# Board_v_02b.net
KiCad netlist of a schematic drawn in EAGLE
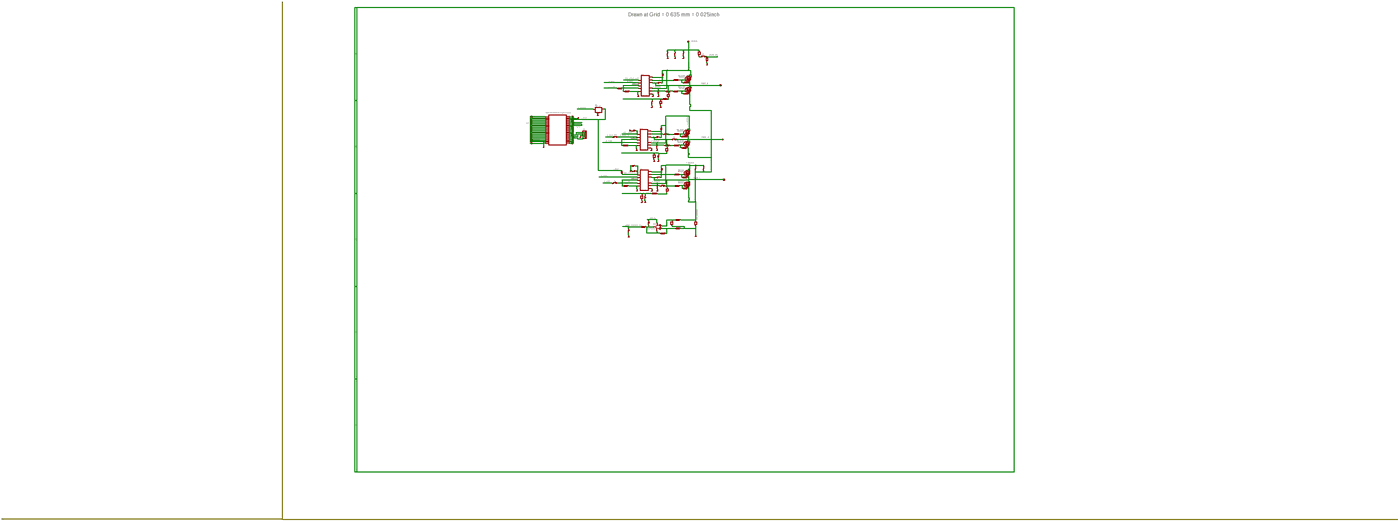
[diagram p0: schematic, sheet 1, overview]
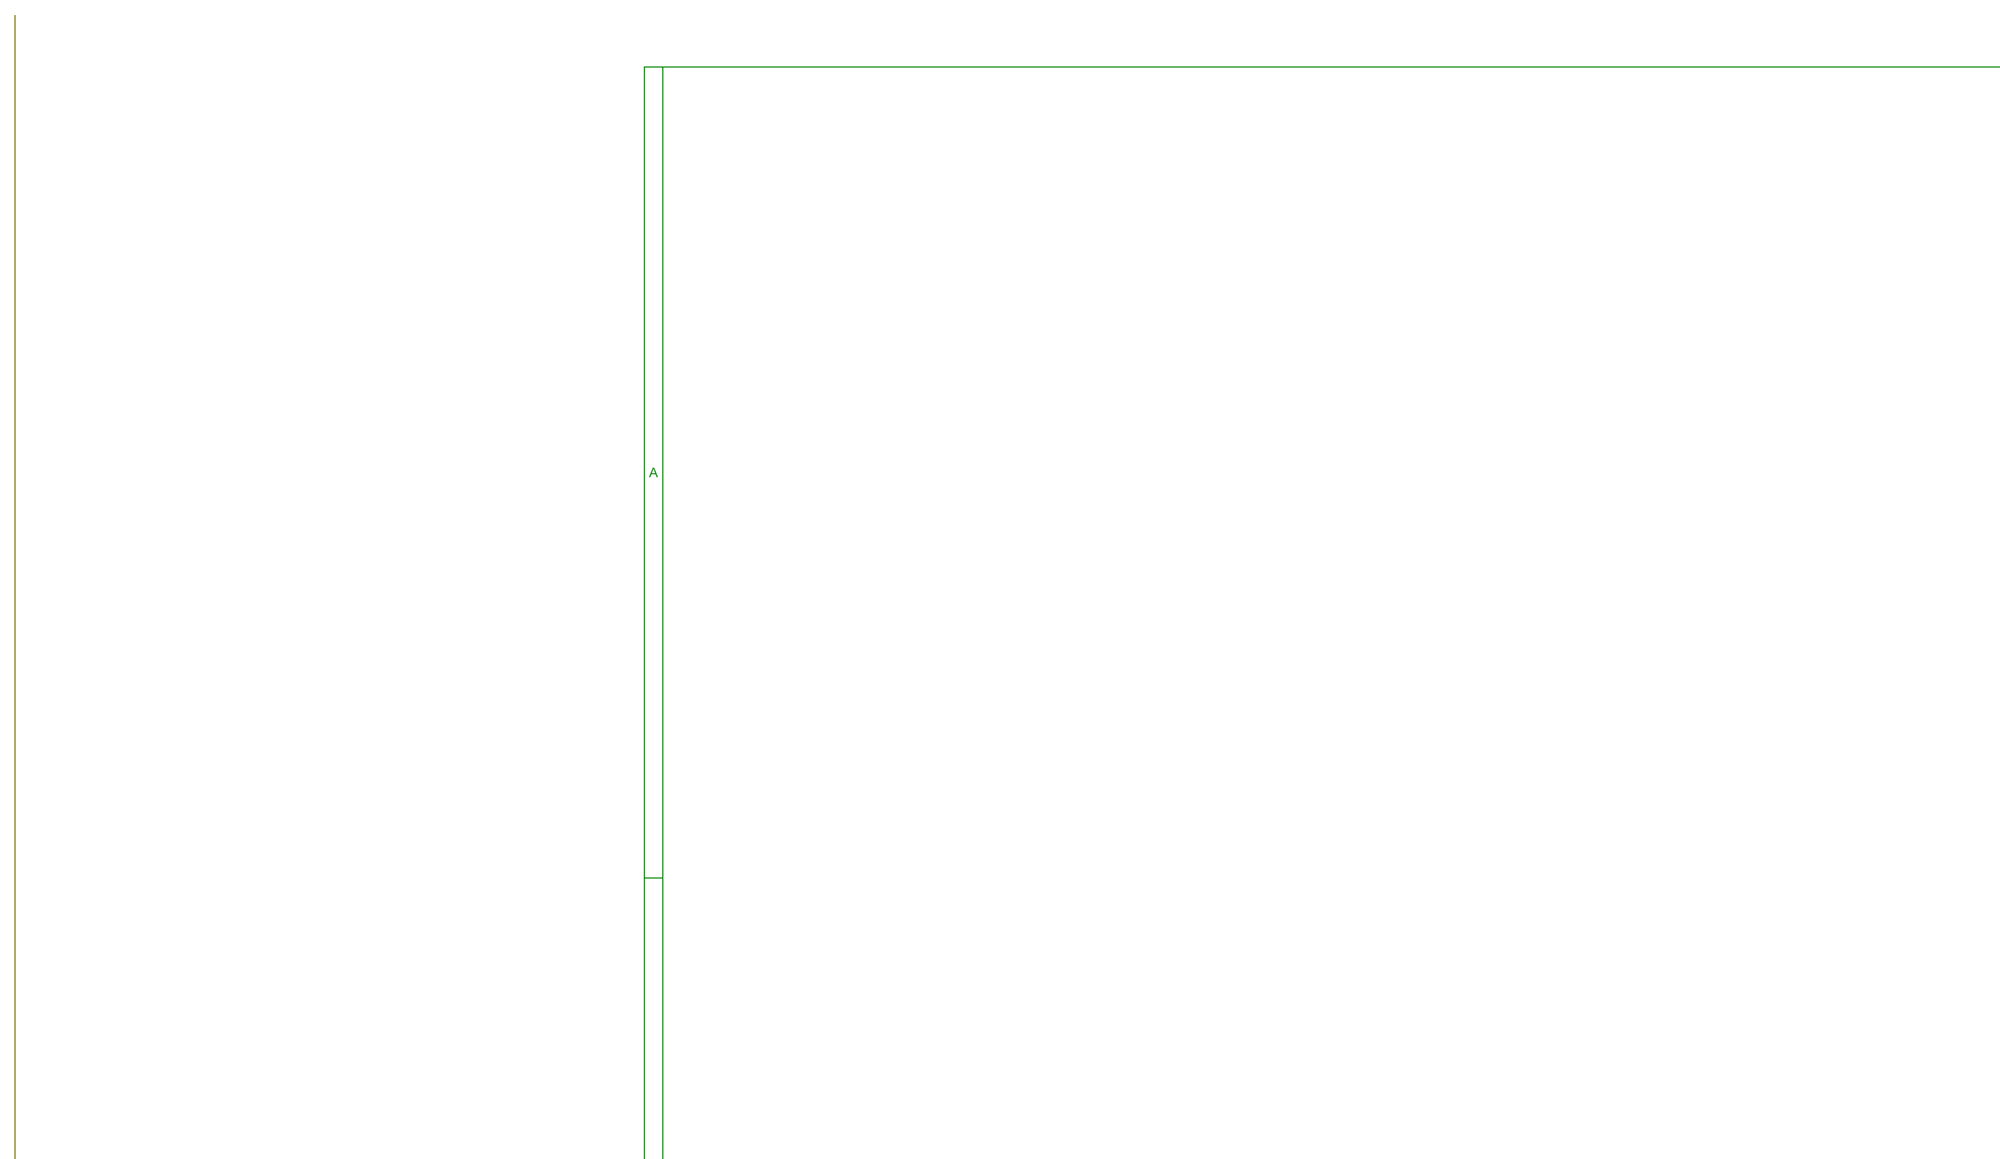
[diagram p1: schematic, sheet 1, part 1 of 7]
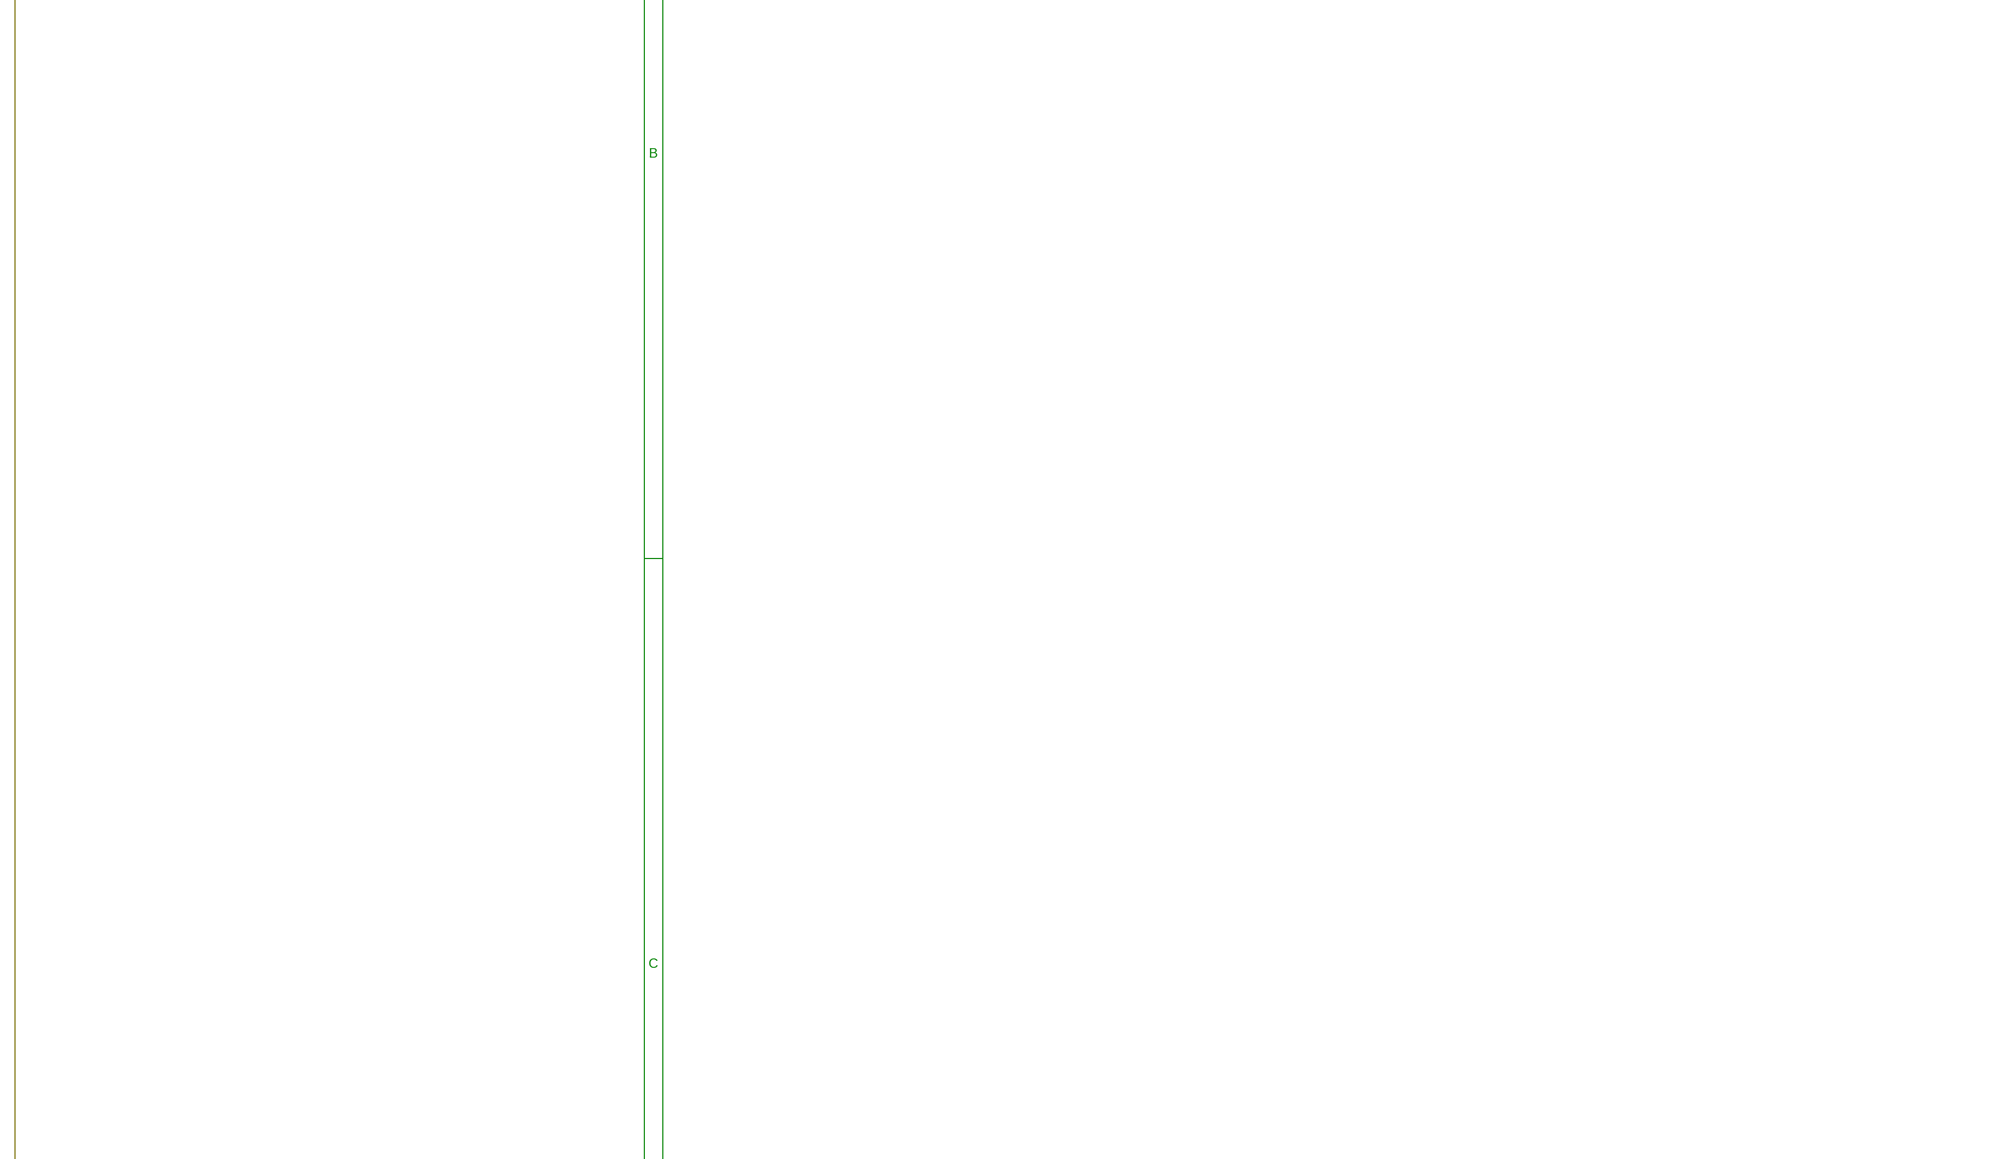
[diagram p2: schematic, sheet 1, part 2 of 7]
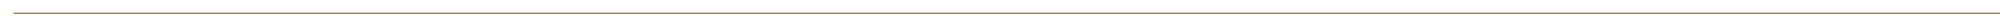
[diagram p3: schematic, sheet 1, part 3 of 7]
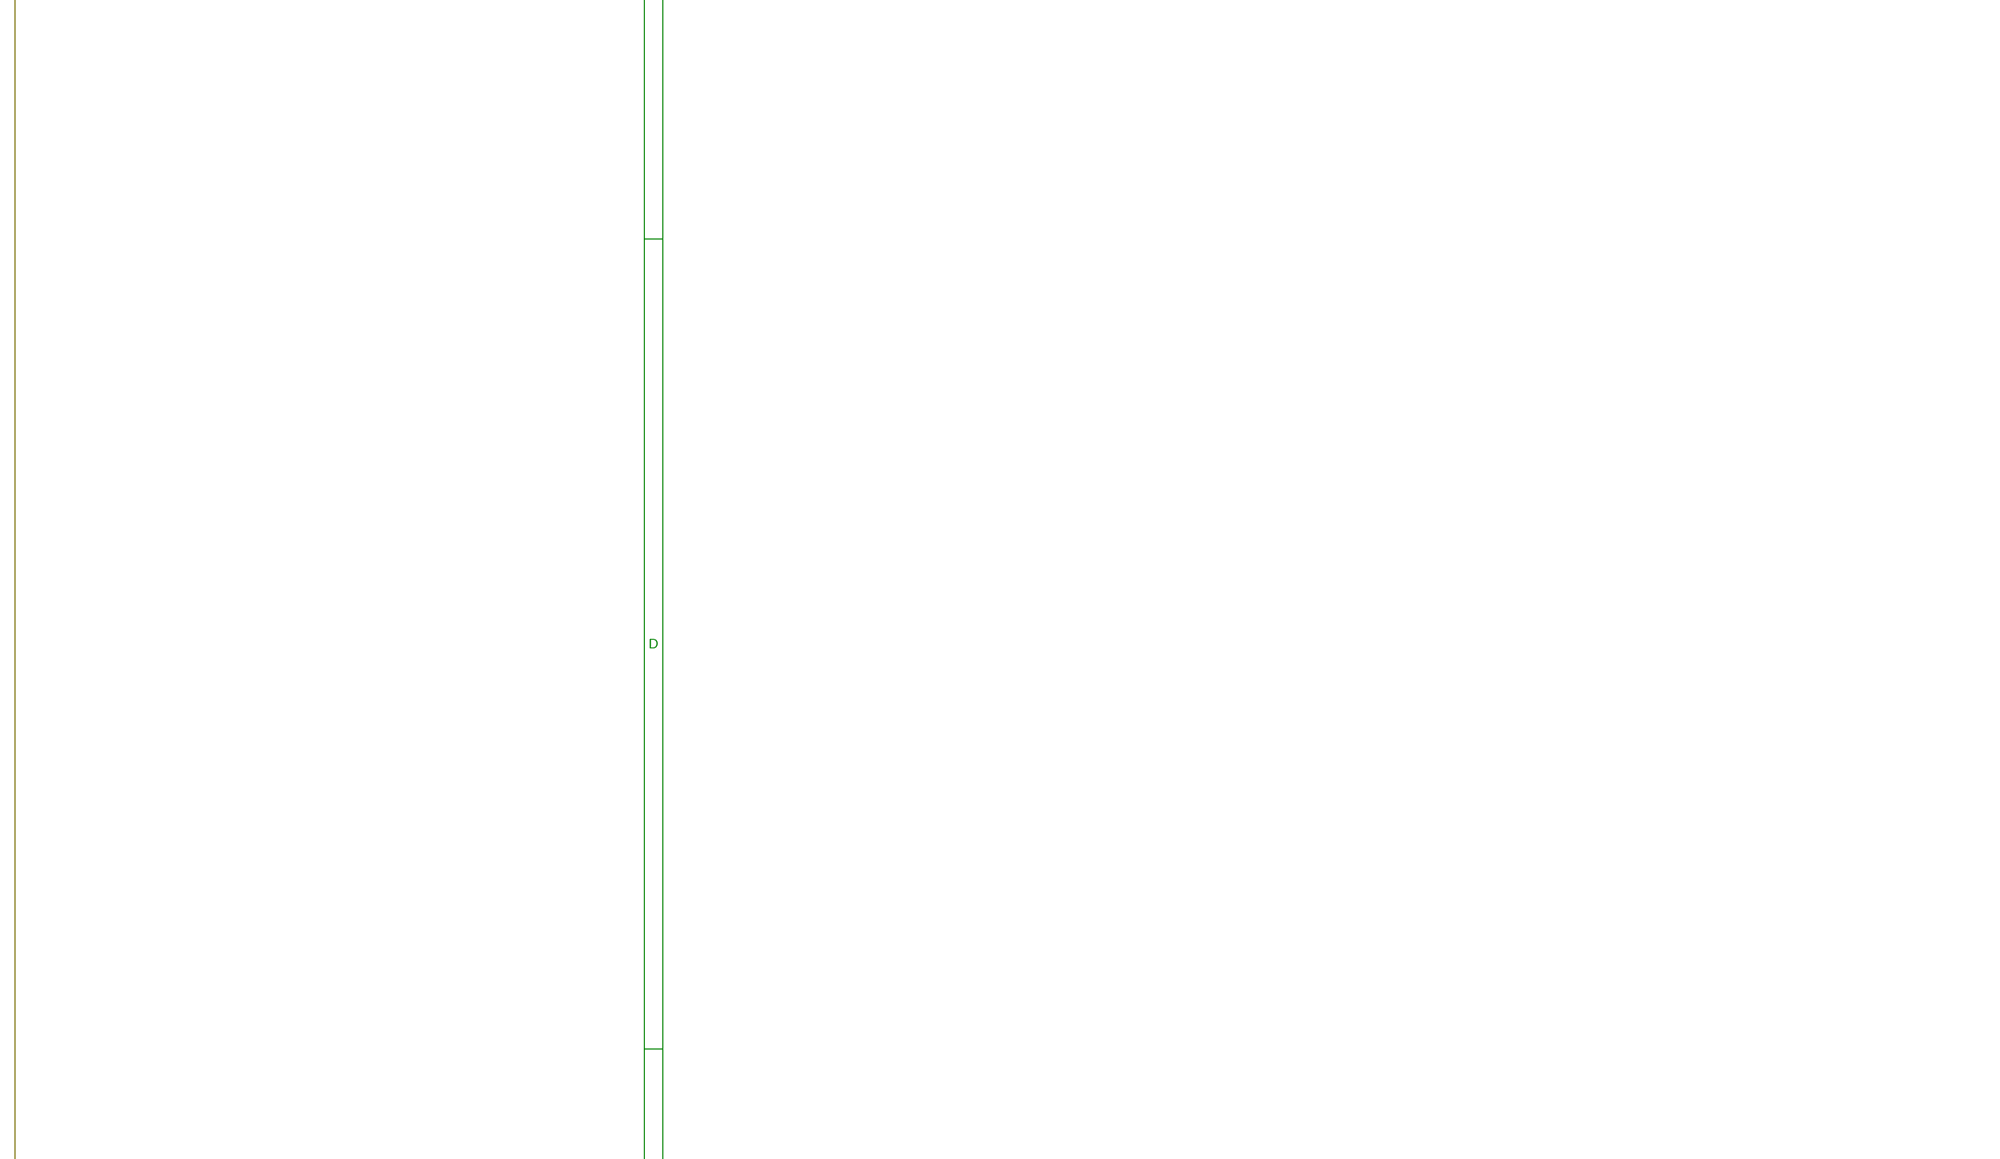
[diagram p4: schematic, sheet 1, part 4 of 7]
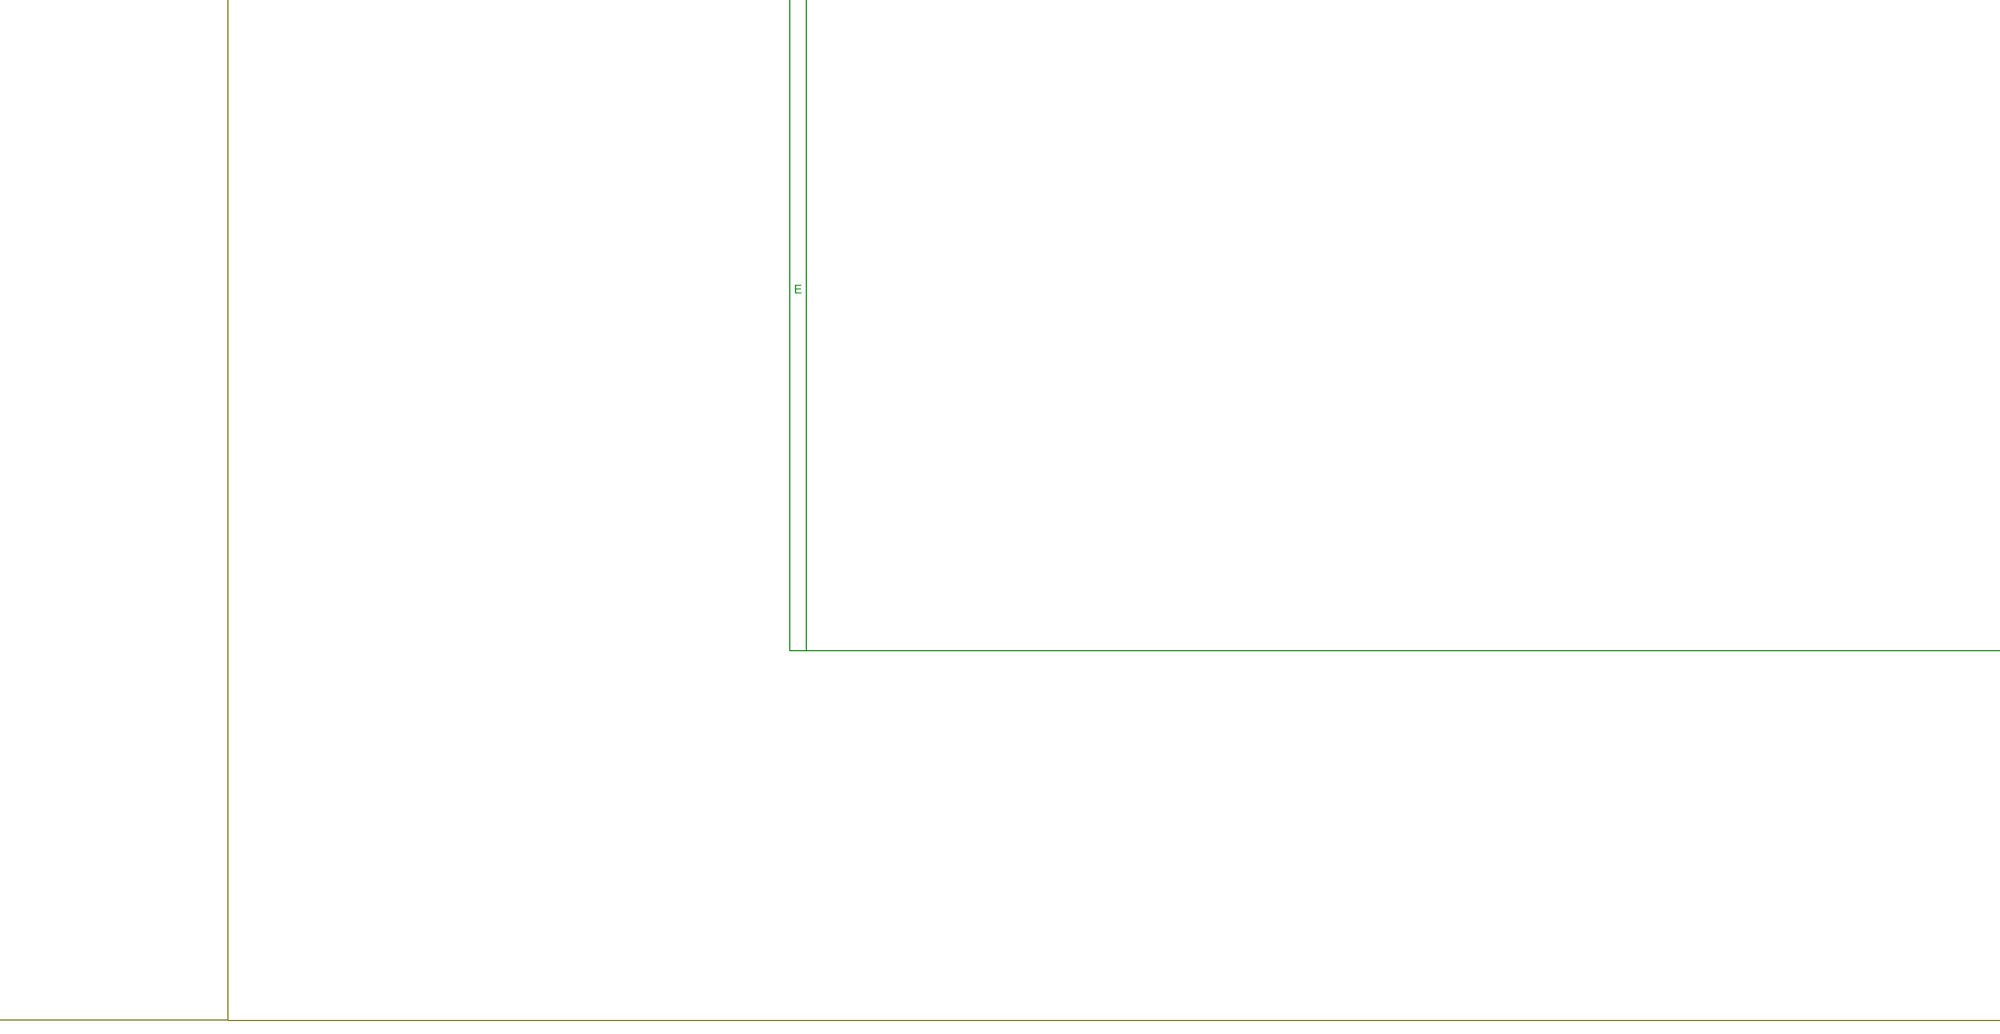
[diagram p5: schematic, sheet 1, part 5 of 7]
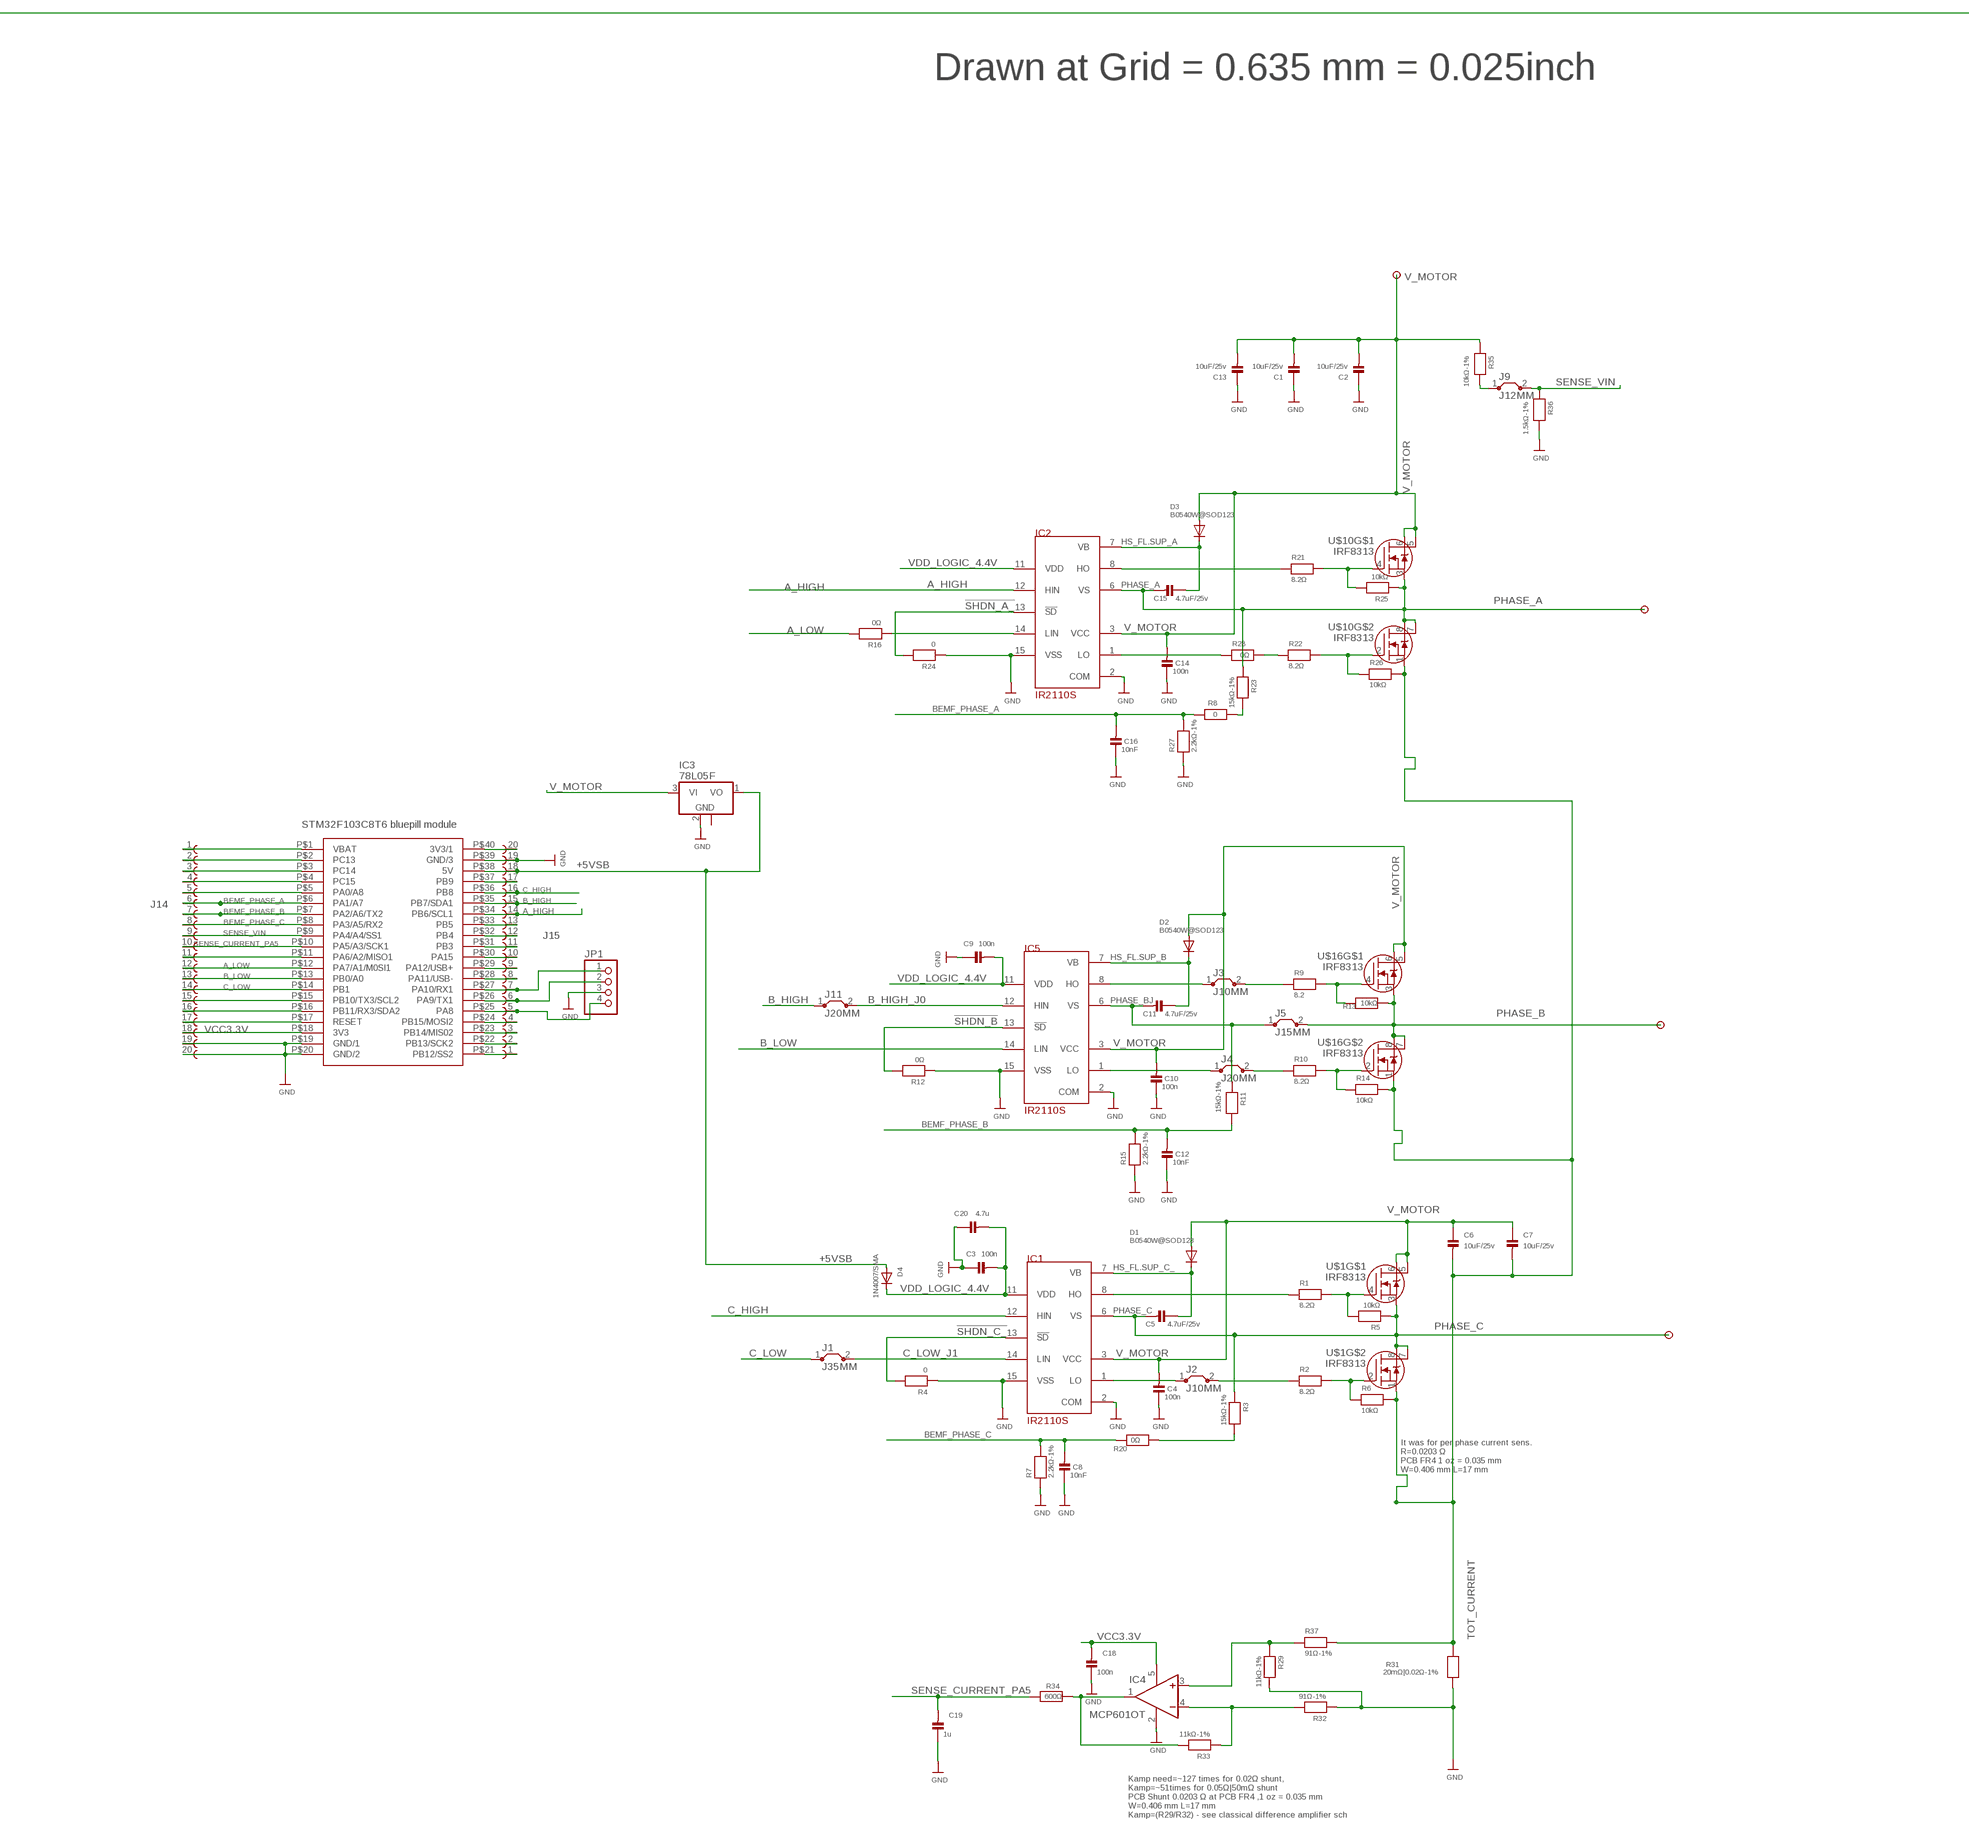
[diagram p6: schematic, sheet 1, part 6 of 7]
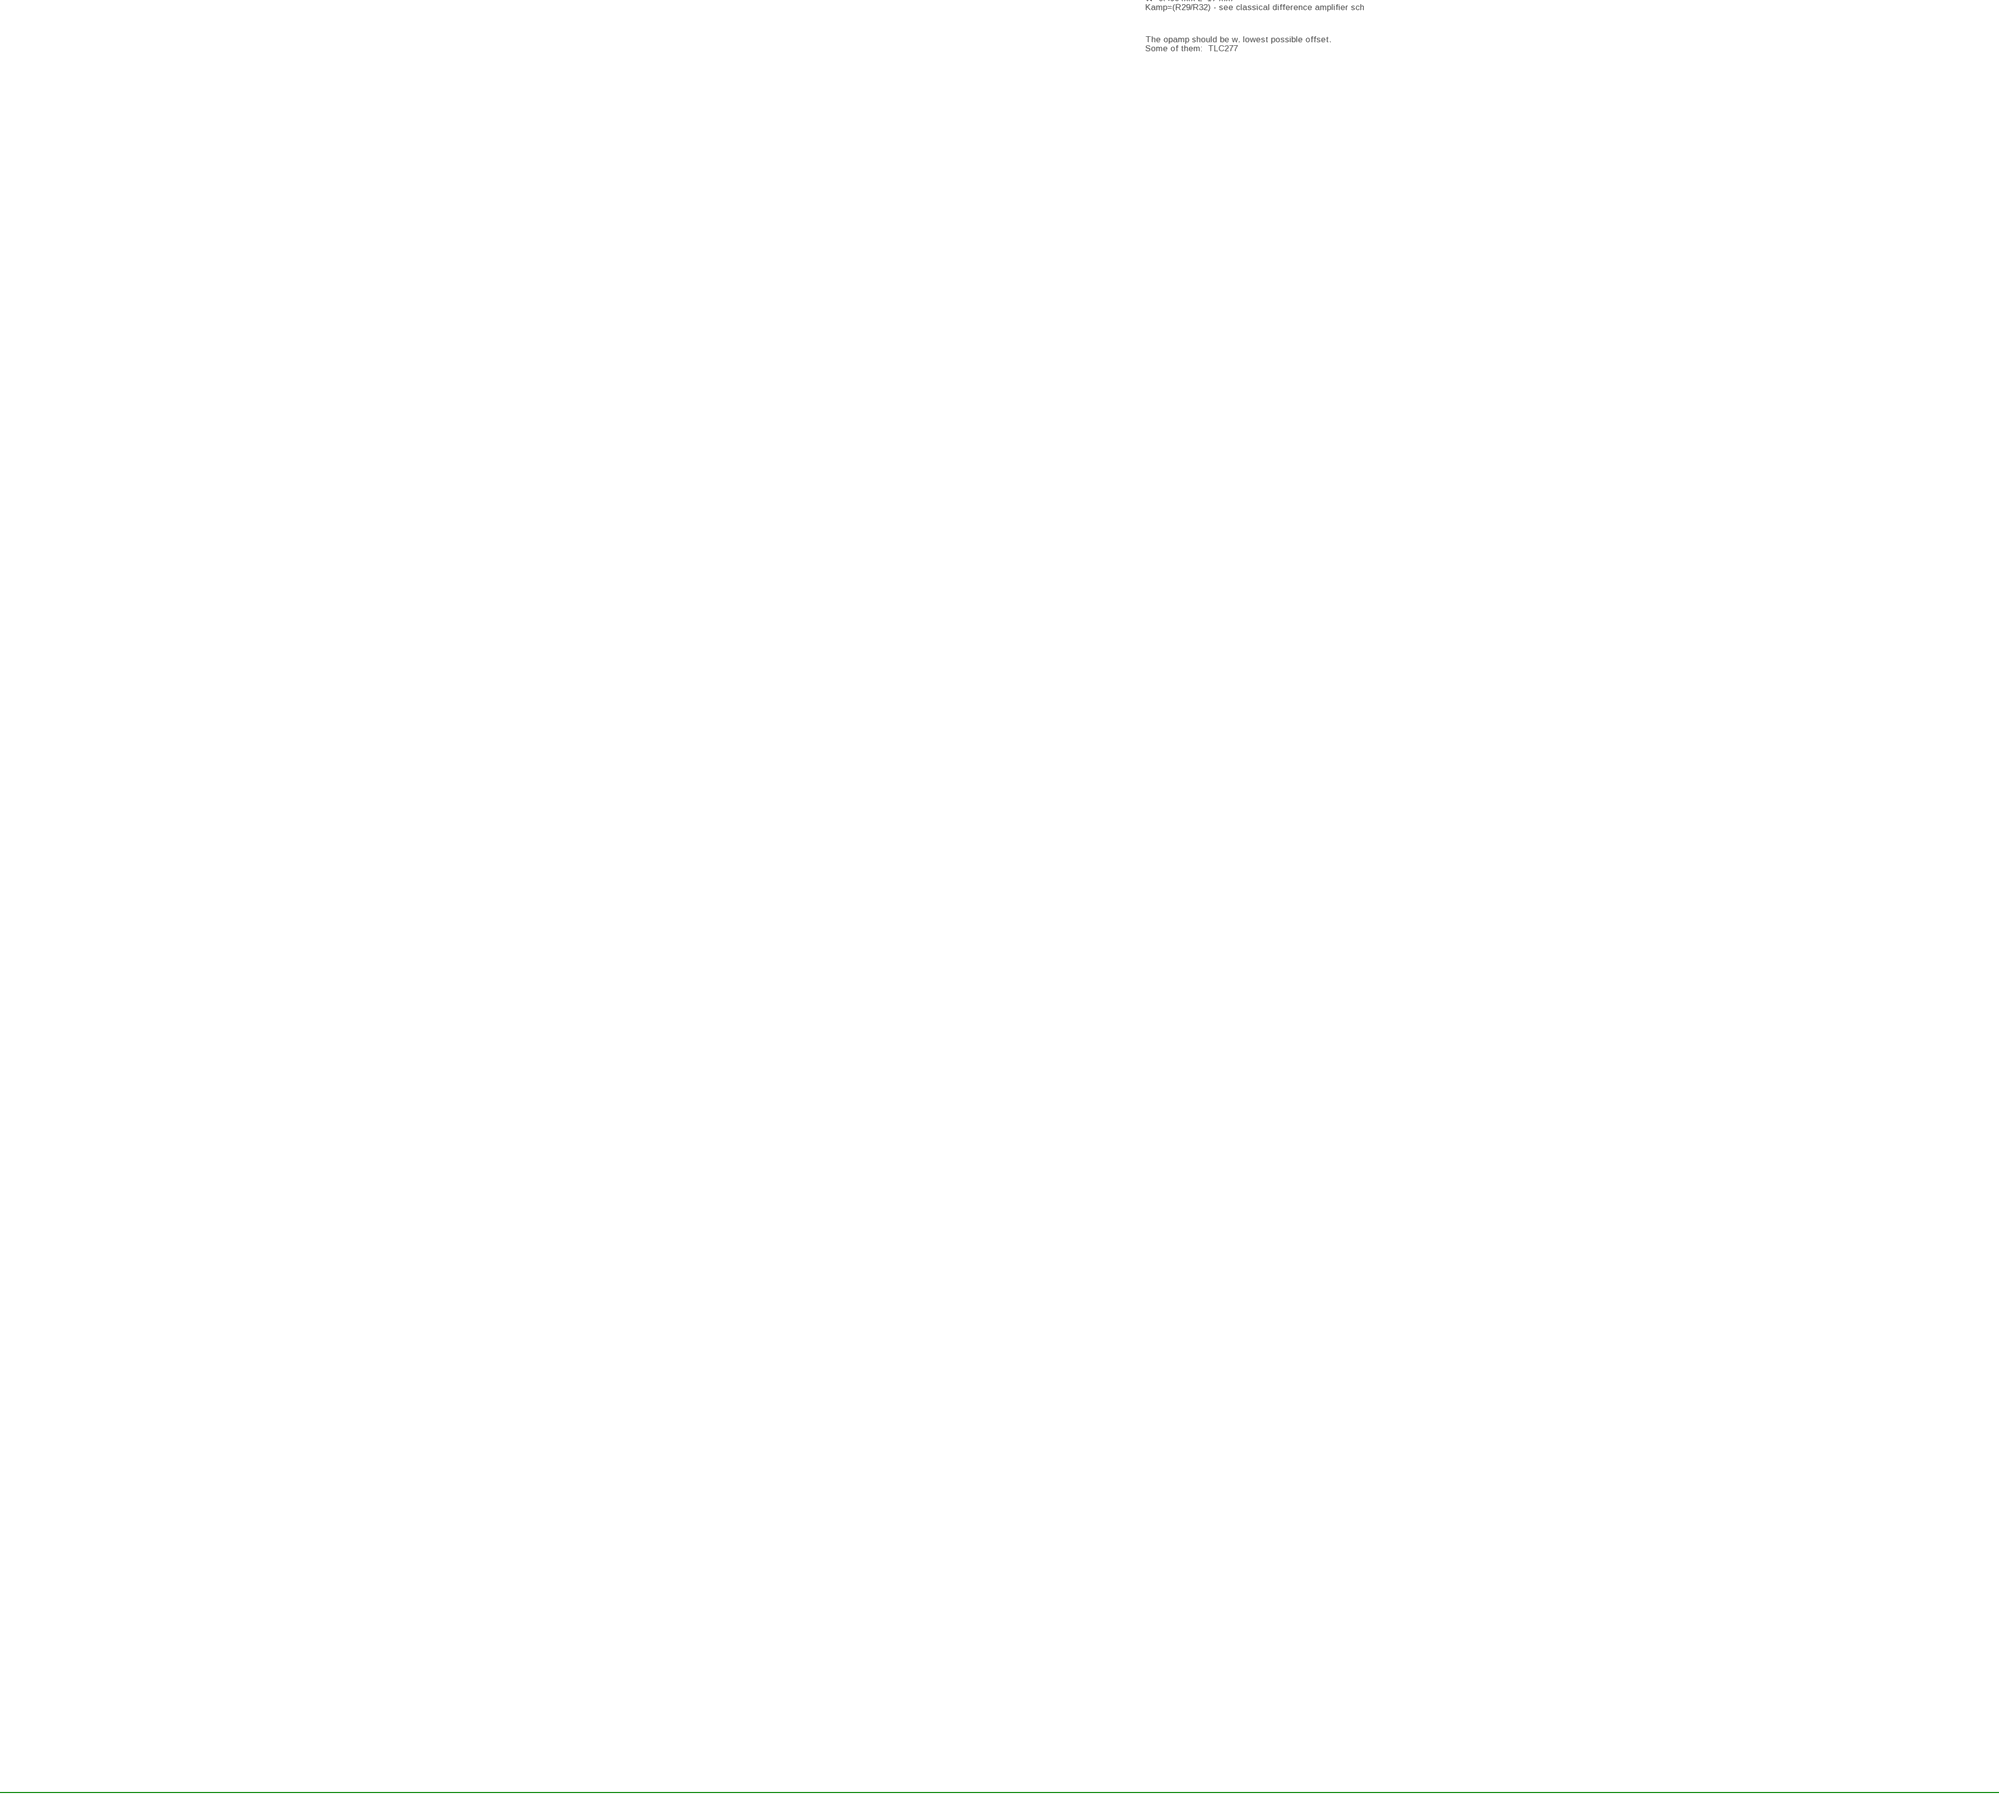
[diagram p7: schematic, sheet 1, part 7 of 7]

(export (version "E")
  (design (tool "Eeschema 10.0.6"))
  (components
    (comp (ref "BLUEPILL-STM32F103C8T6_MODULE")
      (value "BLUEPILL")
      (footprint "eagle-import:40-DIP-BLUE-PIL")
      (fields (field (name "NAME1") "STM32F103C8T6 bluepill module"))
      (libsource (lib "eagle-import") (part "BLUEPILL"))
    )
    (comp (ref "C1")
      (value "10uF/25v")
      (footprint "eagle-import:_0805MP")
      (libsource (lib "eagle-import") (part "CAP_CERAMIC_0805MP"))
    )
    (comp (ref "C2")
      (value "10uF/25v")
      (footprint "eagle-import:_0805MP")
      (libsource (lib "eagle-import") (part "CAP_CERAMIC_0805MP"))
    )
    (comp (ref "C3")
      (value "100n")
      (footprint "eagle-import:_0805MP")
      (libsource (lib "eagle-import") (part "CAP_CERAMIC_0805MP"))
    )
    (comp (ref "C4")
      (value "100n")
      (footprint "eagle-import:_0603MP")
      (libsource (lib "eagle-import") (part "CAP_CERAMIC_0603MP"))
    )
    (comp (ref "C5")
      (value "4.7uF/25v")
      (footprint "eagle-import:_0805MP")
      (libsource (lib "eagle-import") (part "CAP_CERAMIC_0805MP"))
    )
    (comp (ref "C6")
      (value "10uF/25v")
      (footprint "eagle-import:_0805MP")
      (libsource (lib "eagle-import") (part "CAP_CERAMIC_0805MP"))
    )
    (comp (ref "C7")
      (value "10uF/25v")
      (footprint "eagle-import:_0805MP")
      (libsource (lib "eagle-import") (part "CAP_CERAMIC_0805MP"))
    )
    (comp (ref "C8")
      (value "10nF")
      (footprint "eagle-import:_0805MP")
      (libsource (lib "eagle-import") (part "CAP_CERAMIC_0805MP"))
    )
    (comp (ref "C9")
      (value "100n")
      (footprint "eagle-import:_0603MP")
      (libsource (lib "eagle-import") (part "CAP_CERAMIC_0603MP"))
    )
    (comp (ref "C10")
      (value "100n")
      (footprint "eagle-import:_0603MP")
      (libsource (lib "eagle-import") (part "CAP_CERAMIC_0603MP"))
    )
    (comp (ref "C11")
      (value "4.7uF/25v")
      (footprint "eagle-import:_0805MP")
      (libsource (lib "eagle-import") (part "CAP_CERAMIC_0805MP"))
    )
    (comp (ref "C12")
      (value "10nF")
      (footprint "eagle-import:_0805MP")
      (libsource (lib "eagle-import") (part "CAP_CERAMIC_0805MP"))
    )
    (comp (ref "C13")
      (value "10uF/25v")
      (footprint "eagle-import:_0805MP")
      (libsource (lib "eagle-import") (part "CAP_CERAMIC_0805MP"))
    )
    (comp (ref "C14")
      (value "100n")
      (footprint "eagle-import:_0603MP")
      (libsource (lib "eagle-import") (part "CAP_CERAMIC_0603MP"))
    )
    (comp (ref "C15")
      (value "4.7uF/25v")
      (footprint "eagle-import:_0805MP")
      (libsource (lib "eagle-import") (part "CAP_CERAMIC_0805MP"))
    )
    (comp (ref "C16")
      (value "10nF")
      (footprint "eagle-import:_0805MP")
      (libsource (lib "eagle-import") (part "CAP_CERAMIC_0805MP"))
    )
    (comp (ref "C18")
      (value "100n")
      (footprint "eagle-import:_0805MP")
      (libsource (lib "eagle-import") (part "CAP_CERAMIC_0805MP"))
    )
    (comp (ref "C19")
      (value "1u")
      (footprint "eagle-import:_0805MP")
      (libsource (lib "eagle-import") (part "CAP_CERAMIC_0805MP"))
    )
    (comp (ref "C20")
      (value "4.7u")
      (footprint "eagle-import:_0805MP")
      (libsource (lib "eagle-import") (part "CAP_CERAMIC_0805MP"))
    )
    (comp (ref "D1")
      (value "B0540W@SOD123")
      (footprint "eagle-import:SOD-123")
      (libsource (lib "eagle-import") (part "DIODESOD-123"))
    )
    (comp (ref "D2")
      (value "B0540W@SOD123")
      (footprint "eagle-import:SOD-123")
      (libsource (lib "eagle-import") (part "DIODESOD-123"))
    )
    (comp (ref "D3")
      (value "B0540W@SOD123")
      (footprint "eagle-import:SOD-123")
      (libsource (lib "eagle-import") (part "DIODESOD-123"))
    )
    (comp (ref "D4")
      (value "1N4007/SMA")
      (footprint "eagle-import:SMADIODE")
      (libsource (lib "eagle-import") (part "DIODESMA"))
    )
    (comp (ref "IC1")
      (value "IR2110S")
      (footprint "eagle-import:SO-16DW")
      (libsource (lib "eagle-import") (part "IR2110S"))
    )
    (comp (ref "IC2")
      (value "IR2110S")
      (footprint "eagle-import:SO-16DW")
      (libsource (lib "eagle-import") (part "IR2110S"))
    )
    (comp (ref "IC3")
      (value "78L05F")
      (footprint "eagle-import:SOT89")
      (libsource (lib "eagle-import") (part "78LF05"))
    )
    (comp (ref "IC4")
      (value "MCP601OT")
      (footprint "eagle-import:SOT23-5")
      (libsource (lib "eagle-import") (part "MCP601OT"))
    )
    (comp (ref "IC5")
      (value "IR2110S")
      (footprint "eagle-import:SO-16DW")
      (libsource (lib "eagle-import") (part "IR2110S"))
    )
    (comp (ref "J1")
      (value "J35MM")
      (footprint "eagle-import:J35MM")
      (libsource (lib "eagle-import") (part "J35MM"))
    )
    (comp (ref "J2")
      (value "J10MM")
      (footprint "eagle-import:10")
      (libsource (lib "eagle-import") (part "jumper_J10MM"))
    )
    (comp (ref "J3")
      (value "J10MM")
      (footprint "eagle-import:10")
      (libsource (lib "eagle-import") (part "jumper_J10MM"))
    )
    (comp (ref "J4")
      (value "J20MM")
      (footprint "eagle-import:20")
      (libsource (lib "eagle-import") (part "jumper_J20MM"))
    )
    (comp (ref "J5")
      (value "J15MM")
      (footprint "eagle-import:15")
      (libsource (lib "eagle-import") (part "jumper_J15MM"))
    )
    (comp (ref "J9")
      (value "J12MM")
      (footprint "eagle-import:12")
      (libsource (lib "eagle-import") (part "jumper_J12MM"))
    )
    (comp (ref "J11")
      (value "J20MM")
      (footprint "eagle-import:20")
      (libsource (lib "eagle-import") (part "jumper_J20MM"))
    )
    (comp (ref "J14")
      (value "61002013321")
      (footprint "eagle-import:CON-20PIN-SMD-MANUALLY-BENT-FROM-NON-SMD")
      (libsource (lib "eagle-import") (part "61002013321"))
    )
    (comp (ref "J15")
      (value "61002013321")
      (footprint "eagle-import:CON-20PIN-SMD-MANUALLY-BENT-FROM-NON-SMD")
      (libsource (lib "eagle-import") (part "61002013321"))
    )
    (comp (ref "JP1")
      (value "PINHD-1X04_2.54-SMD")
      (footprint "eagle-import:1X04SMD")
      (libsource (lib "eagle-import") (part "PINHD-1X04_2.54-SMD"))
    )
    (comp (ref "PHASE_A")
      (value "PHASE_A")
      (footprint "eagle-import:PAD")
      (libsource (lib "eagle-import") (part "PAD"))
    )
    (comp (ref "PHASE_B")
      (value "PHASE_B")
      (footprint "eagle-import:PAD")
      (libsource (lib "eagle-import") (part "PAD"))
    )
    (comp (ref "PHASE_C")
      (value "PHASE_C")
      (footprint "eagle-import:PAD")
      (libsource (lib "eagle-import") (part "PAD"))
    )
    (comp (ref "R1")
      (value "8.2Ω")
      (footprint "eagle-import:_0805MP")
      (libsource (lib "eagle-import") (part "RESISTOR_0805MP"))
    )
    (comp (ref "R2")
      (value "8.2Ω")
      (footprint "eagle-import:_0805MP")
      (libsource (lib "eagle-import") (part "RESISTOR_0805MP"))
    )
    (comp (ref "R3")
      (value "15kΩ-1%")
      (footprint "eagle-import:_0805MP")
      (libsource (lib "eagle-import") (part "RESISTOR_0805MP"))
    )
    (comp (ref "R4")
      (value "0")
      (footprint "eagle-import:_0805MP")
      (libsource (lib "eagle-import") (part "RESISTOR_0805MP"))
    )
    (comp (ref "R5")
      (value "10kΩ")
      (footprint "eagle-import:_0805MP")
      (libsource (lib "eagle-import") (part "RESISTOR_0805MP"))
    )
    (comp (ref "R6")
      (value "10kΩ")
      (footprint "eagle-import:_0805MP")
      (libsource (lib "eagle-import") (part "RESISTOR_0805MP"))
    )
    (comp (ref "R7")
      (value "2.2kΩ-1%")
      (footprint "eagle-import:_0805MP")
      (libsource (lib "eagle-import") (part "RESISTOR_0805MP"))
    )
    (comp (ref "R8")
      (value "0")
      (footprint "eagle-import:_0805MP")
      (libsource (lib "eagle-import") (part "RESISTOR_0805MP"))
    )
    (comp (ref "R9")
      (value "8.2")
      (footprint "eagle-import:_0805MP")
      (libsource (lib "eagle-import") (part "RESISTOR_0805MP"))
    )
    (comp (ref "R10")
      (value "8.2Ω")
      (footprint "eagle-import:_0805MP")
      (libsource (lib "eagle-import") (part "RESISTOR_0805MP"))
    )
    (comp (ref "R11")
      (value "15kΩ-1%")
      (footprint "eagle-import:_0805MP")
      (libsource (lib "eagle-import") (part "RESISTOR_0805MP"))
    )
    (comp (ref "R12")
      (value "0Ω")
      (footprint "eagle-import:_0805MP")
      (libsource (lib "eagle-import") (part "RESISTOR_0805MP"))
    )
    (comp (ref "R13")
      (value "10kΩ")
      (footprint "eagle-import:_0805MP")
      (libsource (lib "eagle-import") (part "RESISTOR_0805MP"))
    )
    (comp (ref "R14")
      (value "10kΩ")
      (footprint "eagle-import:_0805MP")
      (libsource (lib "eagle-import") (part "RESISTOR_0805MP"))
    )
    (comp (ref "R15")
      (value "2.2kΩ-1%")
      (footprint "eagle-import:_0805MP")
      (libsource (lib "eagle-import") (part "RESISTOR_0805MP"))
    )
    (comp (ref "R16")
      (value "0Ω")
      (footprint "eagle-import:_0805MP")
      (libsource (lib "eagle-import") (part "RESISTOR_0805MP"))
    )
    (comp (ref "R20")
      (value "0Ω")
      (footprint "eagle-import:_0805MP")
      (libsource (lib "eagle-import") (part "RESISTOR_0805MP"))
    )
    (comp (ref "R21")
      (value "8.2Ω")
      (footprint "eagle-import:_0805MP")
      (libsource (lib "eagle-import") (part "RESISTOR_0805MP"))
    )
    (comp (ref "R22")
      (value "8.2Ω")
      (footprint "eagle-import:_0805MP")
      (libsource (lib "eagle-import") (part "RESISTOR_0805MP"))
    )
    (comp (ref "R23")
      (value "15kΩ-1%")
      (footprint "eagle-import:_0805MP")
      (libsource (lib "eagle-import") (part "RESISTOR_0805MP"))
    )
    (comp (ref "R24")
      (value "0")
      (footprint "eagle-import:_0805MP")
      (libsource (lib "eagle-import") (part "RESISTOR_0805MP"))
    )
    (comp (ref "R25")
      (value "10kΩ")
      (footprint "eagle-import:_0805MP")
      (libsource (lib "eagle-import") (part "RESISTOR_0805MP"))
    )
    (comp (ref "R26")
      (value "10kΩ")
      (footprint "eagle-import:_0805MP")
      (libsource (lib "eagle-import") (part "RESISTOR_0805MP"))
    )
    (comp (ref "R27")
      (value "2.2kΩ-1%")
      (footprint "eagle-import:_0805MP")
      (libsource (lib "eagle-import") (part "RESISTOR_0805MP"))
    )
    (comp (ref "R28")
      (value "0Ω")
      (footprint "eagle-import:_0805MP")
      (libsource (lib "eagle-import") (part "RESISTOR_0805MP"))
    )
    (comp (ref "R29")
      (value "11kΩ-1%")
      (footprint "eagle-import:_0805MP")
      (libsource (lib "eagle-import") (part "RESISTOR_0805MP"))
    )
    (comp (ref "R31")
      (value "20mΩ|0.02Ω-1%")
      (footprint "eagle-import:2512")
      (libsource (lib "eagle-import") (part "RESISTOR2512"))
    )
    (comp (ref "R32")
      (value "91Ω-1%")
      (footprint "eagle-import:_0805MP")
      (libsource (lib "eagle-import") (part "RESISTOR_0805MP"))
    )
    (comp (ref "R33")
      (value "11kΩ-1%")
      (footprint "eagle-import:_0805MP")
      (libsource (lib "eagle-import") (part "RESISTOR_0805MP"))
    )
    (comp (ref "R34")
      (value "600Ω")
      (footprint "eagle-import:_0805MP")
      (libsource (lib "eagle-import") (part "RESISTOR_0805MP"))
    )
    (comp (ref "R35")
      (value "10kΩ-1%")
      (footprint "eagle-import:_0805MP")
      (libsource (lib "eagle-import") (part "RESISTOR_0805MP"))
    )
    (comp (ref "R36")
      (value "1.5kΩ-1%")
      (footprint "eagle-import:_0805MP")
      (libsource (lib "eagle-import") (part "RESISTOR_0805MP"))
    )
    (comp (ref "R37")
      (value "91Ω-1%")
      (footprint "eagle-import:_0805MP")
      (libsource (lib "eagle-import") (part "RESISTOR_0805MP"))
    )
    (comp (ref "U$1")
      (value "IRF8313")
      (footprint "eagle-import:SO08")
      (libsource (lib "eagle-import") (part "IRF8313"))
    )
    (comp (ref "U$10")
      (value "IRF8313")
      (footprint "eagle-import:SO08")
      (libsource (lib "eagle-import") (part "IRF8313"))
    )
    (comp (ref "U$16")
      (value "IRF8313")
      (footprint "eagle-import:SO08")
      (libsource (lib "eagle-import") (part "IRF8313"))
    )
    (comp (ref "V_MOTOR")
      (value "V_MOTOR")
      (footprint "eagle-import:PAD")
      (libsource (lib "eagle-import") (part "PAD"))
    )
  )
  (nets
    (net (code "1") (name "/+5VSB") (class "Default")
      (node (ref "BLUEPILL-STM32F103C8T6_MODULE") (pin "P$38") (pinfunction "5V_P$38") (pintype "bidirectional"))
      (node (ref "D4") (pin "A") (pinfunction "A_A") (pintype "passive"))
      (node (ref "IC3") (pin "1") (pinfunction "VO_1") (pintype "passive"))
      (node (ref "J15") (pin "18") (pinfunction "18_18") (pintype "passive"))
    )
    (net (code "2") (name "/A_HIGH") (class "Default")
      (node (ref "BLUEPILL-STM32F103C8T6_MODULE") (pin "P$34") (pinfunction "PB6/SCL1_P$34") (pintype "bidirectional"))
      (node (ref "IC2") (pin "12") (pinfunction "HIN_12") (pintype "input"))
      (node (ref "J15") (pin "14") (pinfunction "14_14") (pintype "passive"))
    )
    (net (code "3") (name "/A_LOW") (class "Default")
      (node (ref "BLUEPILL-STM32F103C8T6_MODULE") (pin "P$12") (pinfunction "PA7/A1/M0SI1_P$12") (pintype "bidirectional"))
      (node (ref "J14") (pin "12") (pinfunction "12_12") (pintype "passive"))
      (node (ref "R16") (pin "2") (pinfunction "2_2") (pintype "passive"))
    )
    (net (code "4") (name "/BEMF_PHASE_A") (class "Default")
      (node (ref "BLUEPILL-STM32F103C8T6_MODULE") (pin "P$6") (pinfunction "PA1/A7_P$6") (pintype "bidirectional"))
      (node (ref "C16") (pin "2") (pinfunction "P$2_2") (pintype "passive"))
      (node (ref "J14") (pin "6") (pinfunction "6_6") (pintype "passive"))
      (node (ref "R27") (pin "2") (pinfunction "2_2") (pintype "passive"))
      (node (ref "R8") (pin "1") (pinfunction "1_1") (pintype "passive"))
    )
    (net (code "5") (name "/BEMF_PHASE_B") (class "Default")
      (node (ref "BLUEPILL-STM32F103C8T6_MODULE") (pin "P$7") (pinfunction "PA2/A6/TX2_P$7") (pintype "bidirectional"))
      (node (ref "C12") (pin "2") (pinfunction "P$2_2") (pintype "passive"))
      (node (ref "J14") (pin "7") (pinfunction "7_7") (pintype "passive"))
      (node (ref "R11") (pin "2") (pinfunction "2_2") (pintype "passive"))
      (node (ref "R15") (pin "2") (pinfunction "2_2") (pintype "passive"))
    )
    (net (code "6") (name "/BEMF_PHASE_C") (class "Default")
      (node (ref "BLUEPILL-STM32F103C8T6_MODULE") (pin "P$8") (pinfunction "PA3/A5/RX2_P$8") (pintype "bidirectional"))
      (node (ref "C8") (pin "2") (pinfunction "P$2_2") (pintype "passive"))
      (node (ref "J14") (pin "8") (pinfunction "8_8") (pintype "passive"))
      (node (ref "R20") (pin "2") (pinfunction "2_2") (pintype "passive"))
      (node (ref "R7") (pin "2") (pinfunction "2_2") (pintype "passive"))
    )
    (net (code "7") (name "/B_HIGH") (class "Default")
      (node (ref "BLUEPILL-STM32F103C8T6_MODULE") (pin "P$35") (pinfunction "PB7/SDA1_P$35") (pintype "bidirectional"))
      (node (ref "J11") (pin "1") (pinfunction "1_1") (pintype "passive"))
      (node (ref "J15") (pin "15") (pinfunction "15_15") (pintype "passive"))
    )
    (net (code "8") (name "/B_HIGH_J0") (class "Default")
      (node (ref "IC5") (pin "12") (pinfunction "HIN_12") (pintype "input"))
      (node (ref "J11") (pin "2") (pinfunction "2_2") (pintype "passive"))
    )
    (net (code "9") (name "/B_LOW") (class "Default")
      (node (ref "BLUEPILL-STM32F103C8T6_MODULE") (pin "P$13") (pinfunction "PB0/A0_P$13") (pintype "bidirectional"))
      (node (ref "IC5") (pin "14") (pinfunction "LIN_14") (pintype "input"))
      (node (ref "J14") (pin "13") (pinfunction "13_13") (pintype "passive"))
    )
    (net (code "10") (name "/C_HIGH") (class "Default")
      (node (ref "BLUEPILL-STM32F103C8T6_MODULE") (pin "P$36") (pinfunction "PB8_P$36") (pintype "bidirectional"))
      (node (ref "IC1") (pin "12") (pinfunction "HIN_12") (pintype "input"))
      (node (ref "J15") (pin "16") (pinfunction "16_16") (pintype "passive"))
    )
    (net (code "11") (name "/C_LOW") (class "Default")
      (node (ref "BLUEPILL-STM32F103C8T6_MODULE") (pin "P$14") (pinfunction "PB1_P$14") (pintype "bidirectional"))
      (node (ref "J1") (pin "1") (pinfunction "1_1") (pintype "passive"))
      (node (ref "J14") (pin "14") (pinfunction "14_14") (pintype "passive"))
    )
    (net (code "12") (name "/C_LOW_J1") (class "Default")
      (node (ref "IC1") (pin "14") (pinfunction "LIN_14") (pintype "input"))
      (node (ref "J1") (pin "2") (pinfunction "2_2") (pintype "passive"))
    )
    (net (code "13") (name "/HS_FL.SUP_A") (class "Default")
      (node (ref "C15") (pin "1") (pinfunction "P$1_1") (pintype "passive"))
      (node (ref "D3") (pin "C") (pinfunction "C_C") (pintype "passive"))
      (node (ref "IC2") (pin "7") (pinfunction "VB_7") (pintype "power_in"))
    )
    (net (code "14") (name "/HS_FL.SUP_B") (class "Default")
      (node (ref "C11") (pin "1") (pinfunction "P$1_1") (pintype "passive"))
      (node (ref "D2") (pin "C") (pinfunction "C_C") (pintype "passive"))
      (node (ref "IC5") (pin "7") (pinfunction "VB_7") (pintype "power_in"))
    )
    (net (code "15") (name "/HS_FL.SUP_C_") (class "Default")
      (node (ref "C5") (pin "1") (pinfunction "P$1_1") (pintype "passive"))
      (node (ref "D1") (pin "C") (pinfunction "C_C") (pintype "passive"))
      (node (ref "IC1") (pin "7") (pinfunction "VB_7") (pintype "power_in"))
    )
    (net (code "16") (name "/PHASE_A") (class "Default")
      (node (ref "C15") (pin "2") (pinfunction "P$2_2") (pintype "passive"))
      (node (ref "IC2") (pin "6") (pinfunction "VS_6") (pintype "power_in"))
      (node (ref "PHASE_C") (pin "1") (pinfunction "1_1") (pintype "bidirectional"))
      (node (ref "R23") (pin "1") (pinfunction "1_1") (pintype "passive"))
      (node (ref "R25") (pin "1") (pinfunction "1_1") (pintype "passive"))
      (node (ref "U$10") (pin "3") (pinfunction "S_3") (pintype "bidirectional"))
      (node (ref "U$10") (pin "7") (pinfunction "D_7") (pintype "bidirectional"))
      (node (ref "U$10") (pin "8") (pinfunction "D_8") (pintype "bidirectional"))
    )
    (net (code "17") (name "/PHASE_B") (class "Default")
      (node (ref "J5") (pin "2") (pinfunction "2_2") (pintype "passive"))
      (node (ref "PHASE_B") (pin "1") (pinfunction "1_1") (pintype "bidirectional"))
      (node (ref "R13") (pin "1") (pinfunction "1_1") (pintype "passive"))
      (node (ref "U$16") (pin "3") (pinfunction "S_3") (pintype "bidirectional"))
      (node (ref "U$16") (pin "7") (pinfunction "D_7") (pintype "bidirectional"))
      (node (ref "U$16") (pin "8") (pinfunction "D_8") (pintype "bidirectional"))
    )
    (net (code "18") (name "/PHASE_BJ") (class "Default")
      (node (ref "C11") (pin "2") (pinfunction "P$2_2") (pintype "passive"))
      (node (ref "IC5") (pin "6") (pinfunction "VS_6") (pintype "power_in"))
      (node (ref "J5") (pin "1") (pinfunction "1_1") (pintype "passive"))
      (node (ref "R11") (pin "1") (pinfunction "1_1") (pintype "passive"))
    )
    (net (code "19") (name "/PHASE_C") (class "Default")
      (node (ref "C5") (pin "2") (pinfunction "P$2_2") (pintype "passive"))
      (node (ref "IC1") (pin "6") (pinfunction "VS_6") (pintype "power_in"))
      (node (ref "PHASE_A") (pin "1") (pinfunction "1_1") (pintype "bidirectional"))
      (node (ref "R3") (pin "1") (pinfunction "1_1") (pintype "passive"))
      (node (ref "R5") (pin "1") (pinfunction "1_1") (pintype "passive"))
      (node (ref "U$1") (pin "3") (pinfunction "S_3") (pintype "bidirectional"))
      (node (ref "U$1") (pin "7") (pinfunction "D_7") (pintype "bidirectional"))
      (node (ref "U$1") (pin "8") (pinfunction "D_8") (pintype "bidirectional"))
    )
    (net (code "20") (name "/SENSE_CURRENT_PA5") (class "Default")
      (node (ref "BLUEPILL-STM32F103C8T6_MODULE") (pin "P$10") (pinfunction "PA5/A3/SCK1_P$10") (pintype "bidirectional"))
      (node (ref "C19") (pin "2") (pinfunction "P$2_2") (pintype "passive"))
      (node (ref "J14") (pin "10") (pinfunction "10_10") (pintype "passive"))
      (node (ref "R34") (pin "2") (pinfunction "2_2") (pintype "passive"))
    )
    (net (code "21") (name "/SENSE_VIN") (class "Default")
      (node (ref "BLUEPILL-STM32F103C8T6_MODULE") (pin "P$9") (pinfunction "PA4/A4/SS1_P$9") (pintype "bidirectional"))
      (node (ref "J14") (pin "9") (pinfunction "9_9") (pintype "passive"))
      (node (ref "J9") (pin "2") (pinfunction "2_2") (pintype "passive"))
      (node (ref "R36") (pin "1") (pinfunction "1_1") (pintype "passive"))
    )
    (net (code "22") (name "/TOT_CURRENT") (class "Default")
      (node (ref "C6") (pin "2") (pinfunction "P$2_2") (pintype "passive"))
      (node (ref "C7") (pin "2") (pinfunction "P$2_2") (pintype "passive"))
      (node (ref "R14") (pin "2") (pinfunction "2_2") (pintype "passive"))
      (node (ref "R26") (pin "2") (pinfunction "2_2") (pintype "passive"))
      (node (ref "R31") (pin "1") (pinfunction "1_1") (pintype "passive"))
      (node (ref "R37") (pin "2") (pinfunction "2_2") (pintype "passive"))
      (node (ref "R6") (pin "2") (pinfunction "2_2") (pintype "passive"))
      (node (ref "U$1") (pin "1") (pinfunction "S_1") (pintype "bidirectional"))
      (node (ref "U$10") (pin "1") (pinfunction "S_1") (pintype "bidirectional"))
      (node (ref "U$16") (pin "1") (pinfunction "S_1") (pintype "bidirectional"))
    )
    (net (code "23") (name "/VCC3.3V") (class "Default")
      (node (ref "BLUEPILL-STM32F103C8T6_MODULE") (pin "P$18") (pinfunction "3V3_P$18") (pintype "bidirectional"))
      (node (ref "C18") (pin "2") (pinfunction "P$2_2") (pintype "passive"))
      (node (ref "IC4") (pin "5") (pinfunction "V+_5") (pintype "power_in"))
      (node (ref "J14") (pin "18") (pinfunction "18_18") (pintype "passive"))
    )
    (net (code "24") (name "/VDD_LOGIC_4.4V") (class "Default")
      (node (ref "C20") (pin "2") (pinfunction "P$2_2") (pintype "passive"))
      (node (ref "C3") (pin "2") (pinfunction "P$2_2") (pintype "passive"))
      (node (ref "C9") (pin "2") (pinfunction "P$2_2") (pintype "passive"))
      (node (ref "D4") (pin "C") (pinfunction "C_C") (pintype "passive"))
      (node (ref "IC1") (pin "11") (pinfunction "VDD_11") (pintype "power_in"))
      (node (ref "IC2") (pin "11") (pinfunction "VDD_11") (pintype "power_in"))
      (node (ref "IC5") (pin "11") (pinfunction "VDD_11") (pintype "power_in"))
    )
    (net (code "25") (name "/V_MOTOR") (class "Default")
      (node (ref "C1") (pin "2") (pinfunction "P$2_2") (pintype "passive"))
      (node (ref "C10") (pin "2") (pinfunction "P$2_2") (pintype "passive"))
      (node (ref "C13") (pin "2") (pinfunction "P$2_2") (pintype "passive"))
      (node (ref "C14") (pin "2") (pinfunction "P$2_2") (pintype "passive"))
      (node (ref "C2") (pin "2") (pinfunction "P$2_2") (pintype "passive"))
      (node (ref "C4") (pin "2") (pinfunction "P$2_2") (pintype "passive"))
      (node (ref "C6") (pin "1") (pinfunction "P$1_1") (pintype "passive"))
      (node (ref "C7") (pin "1") (pinfunction "P$1_1") (pintype "passive"))
      (node (ref "D1") (pin "A") (pinfunction "A_A") (pintype "passive"))
      (node (ref "D2") (pin "A") (pinfunction "A_A") (pintype "passive"))
      (node (ref "D3") (pin "A") (pinfunction "A_A") (pintype "passive"))
      (node (ref "IC1") (pin "3") (pinfunction "VCC_3") (pintype "power_in"))
      (node (ref "IC2") (pin "3") (pinfunction "VCC_3") (pintype "power_in"))
      (node (ref "IC3") (pin "3") (pinfunction "VI_3") (pintype "input"))
      (node (ref "IC5") (pin "3") (pinfunction "VCC_3") (pintype "power_in"))
      (node (ref "R35") (pin "1") (pinfunction "1_1") (pintype "passive"))
      (node (ref "U$1") (pin "5") (pinfunction "D_5") (pintype "bidirectional"))
      (node (ref "U$1") (pin "6") (pinfunction "D_6") (pintype "bidirectional"))
      (node (ref "U$10") (pin "5") (pinfunction "D_5") (pintype "bidirectional"))
      (node (ref "U$10") (pin "6") (pinfunction "D_6") (pintype "bidirectional"))
      (node (ref "U$16") (pin "5") (pinfunction "D_5") (pintype "bidirectional"))
      (node (ref "U$16") (pin "6") (pinfunction "D_6") (pintype "bidirectional"))
      (node (ref "V_MOTOR") (pin "1") (pinfunction "1_1") (pintype "bidirectional"))
    )
    (net (code "26") (name "/~{SHDN_A_}") (class "Default")
      (node (ref "IC2") (pin "13") (pinfunction "~{SD}_13") (pintype "input"))
      (node (ref "R24") (pin "2") (pinfunction "2_2") (pintype "passive"))
    )
    (net (code "27") (name "/~{SHDN_B}") (class "Default")
      (node (ref "IC5") (pin "13") (pinfunction "~{SD}_13") (pintype "input"))
      (node (ref "R12") (pin "2") (pinfunction "2_2") (pintype "passive"))
    )
    (net (code "28") (name "/~{SHDN_C_}") (class "Default")
      (node (ref "IC1") (pin "13") (pinfunction "~{SD}_13") (pintype "input"))
      (node (ref "R4") (pin "2") (pinfunction "2_2") (pintype "passive"))
    )
    (net (code "29") (name "GND") (class "Default")
      (node (ref "BLUEPILL-STM32F103C8T6_MODULE") (pin "P$19") (pinfunction "GND/1_P$19") (pintype "bidirectional"))
      (node (ref "BLUEPILL-STM32F103C8T6_MODULE") (pin "P$20") (pinfunction "GND/2_P$20") (pintype "bidirectional"))
      (node (ref "BLUEPILL-STM32F103C8T6_MODULE") (pin "P$39") (pinfunction "GND/3_P$39") (pintype "bidirectional"))
      (node (ref "C1") (pin "1") (pinfunction "P$1_1") (pintype "passive"))
      (node (ref "C10") (pin "1") (pinfunction "P$1_1") (pintype "passive"))
      (node (ref "C12") (pin "1") (pinfunction "P$1_1") (pintype "passive"))
      (node (ref "C13") (pin "1") (pinfunction "P$1_1") (pintype "passive"))
      (node (ref "C14") (pin "1") (pinfunction "P$1_1") (pintype "passive"))
      (node (ref "C16") (pin "1") (pinfunction "P$1_1") (pintype "passive"))
      (node (ref "C18") (pin "1") (pinfunction "P$1_1") (pintype "passive"))
      (node (ref "C19") (pin "1") (pinfunction "P$1_1") (pintype "passive"))
      (node (ref "C2") (pin "1") (pinfunction "P$1_1") (pintype "passive"))
      (node (ref "C20") (pin "1") (pinfunction "P$1_1") (pintype "passive"))
      (node (ref "C3") (pin "1") (pinfunction "P$1_1") (pintype "passive"))
      (node (ref "C4") (pin "1") (pinfunction "P$1_1") (pintype "passive"))
      (node (ref "C8") (pin "1") (pinfunction "P$1_1") (pintype "passive"))
      (node (ref "C9") (pin "1") (pinfunction "P$1_1") (pintype "passive"))
      (node (ref "IC1") (pin "15") (pinfunction "VSS_15") (pintype "power_in"))
      (node (ref "IC1") (pin "2") (pinfunction "COM_2") (pintype "power_in"))
      (node (ref "IC2") (pin "15") (pinfunction "VSS_15") (pintype "power_in"))
      (node (ref "IC2") (pin "2") (pinfunction "COM_2") (pintype "power_in"))
      (node (ref "IC3") (pin "2") (pinfunction "GND_2") (pintype "passive"))
      (node (ref "IC4") (pin "2") (pinfunction "V-_2") (pintype "power_in"))
      (node (ref "IC5") (pin "15") (pinfunction "VSS_15") (pintype "power_in"))
      (node (ref "IC5") (pin "2") (pinfunction "COM_2") (pintype "power_in"))
      (node (ref "J14") (pin "19") (pinfunction "19_19") (pintype "passive"))
      (node (ref "J14") (pin "20") (pinfunction "20_20") (pintype "passive"))
      (node (ref "J15") (pin "19") (pinfunction "19_19") (pintype "passive"))
      (node (ref "JP1") (pin "3") (pinfunction "3_3") (pintype "passive"))
      (node (ref "R12") (pin "1") (pinfunction "1_1") (pintype "passive"))
      (node (ref "R15") (pin "1") (pinfunction "1_1") (pintype "passive"))
      (node (ref "R24") (pin "1") (pinfunction "1_1") (pintype "passive"))
      (node (ref "R27") (pin "1") (pinfunction "1_1") (pintype "passive"))
      (node (ref "R29") (pin "2") (pinfunction "2_2") (pintype "passive"))
      (node (ref "R31") (pin "2") (pinfunction "2_2") (pintype "passive"))
      (node (ref "R32") (pin "1") (pinfunction "1_1") (pintype "passive"))
      (node (ref "R36") (pin "2") (pinfunction "2_2") (pintype "passive"))
      (node (ref "R4") (pin "1") (pinfunction "1_1") (pintype "passive"))
      (node (ref "R7") (pin "1") (pinfunction "1_1") (pintype "passive"))
    )
    (net (code "30") (name "Net-(BLUEPILL-STM32F103C8T6_MODULE-3V3{slash}1)") (class "Default")
      (node (ref "BLUEPILL-STM32F103C8T6_MODULE") (pin "P$40") (pinfunction "3V3/1_P$40") (pintype "bidirectional"))
      (node (ref "J15") (pin "20") (pinfunction "20_20") (pintype "passive"))
    )
    (net (code "31") (name "Net-(BLUEPILL-STM32F103C8T6_MODULE-PA0{slash}A8)") (class "Default")
      (node (ref "BLUEPILL-STM32F103C8T6_MODULE") (pin "P$5") (pinfunction "PA0/A8_P$5") (pintype "bidirectional"))
      (node (ref "J14") (pin "5") (pinfunction "5_5") (pintype "passive"))
    )
    (net (code "32") (name "Net-(BLUEPILL-STM32F103C8T6_MODULE-PA6{slash}A2{slash}MISO1)") (class "Default")
      (node (ref "BLUEPILL-STM32F103C8T6_MODULE") (pin "P$11") (pinfunction "PA6/A2/MISO1_P$11") (pintype "bidirectional"))
      (node (ref "J14") (pin "11") (pinfunction "11_11") (pintype "passive"))
    )
    (net (code "33") (name "Net-(BLUEPILL-STM32F103C8T6_MODULE-PA8)") (class "Default")
      (node (ref "BLUEPILL-STM32F103C8T6_MODULE") (pin "P$25") (pinfunction "PA8_P$25") (pintype "bidirectional"))
      (node (ref "J15") (pin "5") (pinfunction "5_5") (pintype "passive"))
      (node (ref "JP1") (pin "4") (pinfunction "4_4") (pintype "passive"))
    )
    (net (code "34") (name "Net-(BLUEPILL-STM32F103C8T6_MODULE-PA9{slash}TX1)") (class "Default")
      (node (ref "BLUEPILL-STM32F103C8T6_MODULE") (pin "P$26") (pinfunction "PA9/TX1_P$26") (pintype "bidirectional"))
      (node (ref "J15") (pin "6") (pinfunction "6_6") (pintype "passive"))
      (node (ref "JP1") (pin "2") (pinfunction "2_2") (pintype "passive"))
    )
    (net (code "35") (name "Net-(BLUEPILL-STM32F103C8T6_MODULE-PA10{slash}RX1)") (class "Default")
      (node (ref "BLUEPILL-STM32F103C8T6_MODULE") (pin "P$27") (pinfunction "PA10/RX1_P$27") (pintype "bidirectional"))
      (node (ref "J15") (pin "7") (pinfunction "7_7") (pintype "passive"))
      (node (ref "JP1") (pin "1") (pinfunction "1_1") (pintype "passive"))
    )
    (net (code "36") (name "Net-(BLUEPILL-STM32F103C8T6_MODULE-PA11{slash}USB-)") (class "Default")
      (node (ref "BLUEPILL-STM32F103C8T6_MODULE") (pin "P$28") (pinfunction "PA11/USB-_P$28") (pintype "bidirectional"))
      (node (ref "J15") (pin "8") (pinfunction "8_8") (pintype "passive"))
    )
    (net (code "37") (name "Net-(BLUEPILL-STM32F103C8T6_MODULE-PA12{slash}USB+)") (class "Default")
      (node (ref "BLUEPILL-STM32F103C8T6_MODULE") (pin "P$29") (pinfunction "PA12/USB+_P$29") (pintype "bidirectional"))
      (node (ref "J15") (pin "9") (pinfunction "9_9") (pintype "passive"))
    )
    (net (code "38") (name "Net-(BLUEPILL-STM32F103C8T6_MODULE-PA15)") (class "Default")
      (node (ref "BLUEPILL-STM32F103C8T6_MODULE") (pin "P$30") (pinfunction "PA15_P$30") (pintype "bidirectional"))
      (node (ref "J15") (pin "10") (pinfunction "10_10") (pintype "passive"))
    )
    (net (code "39") (name "Net-(BLUEPILL-STM32F103C8T6_MODULE-PB3)") (class "Default")
      (node (ref "BLUEPILL-STM32F103C8T6_MODULE") (pin "P$31") (pinfunction "PB3_P$31") (pintype "bidirectional"))
      (node (ref "J15") (pin "11") (pinfunction "11_11") (pintype "passive"))
    )
    (net (code "40") (name "Net-(BLUEPILL-STM32F103C8T6_MODULE-PB4)") (class "Default")
      (node (ref "BLUEPILL-STM32F103C8T6_MODULE") (pin "P$32") (pinfunction "PB4_P$32") (pintype "bidirectional"))
      (node (ref "J15") (pin "12") (pinfunction "12_12") (pintype "passive"))
    )
    (net (code "41") (name "Net-(BLUEPILL-STM32F103C8T6_MODULE-PB5)") (class "Default")
      (node (ref "BLUEPILL-STM32F103C8T6_MODULE") (pin "P$33") (pinfunction "PB5_P$33") (pintype "bidirectional"))
      (node (ref "J15") (pin "13") (pinfunction "13_13") (pintype "passive"))
    )
    (net (code "42") (name "Net-(BLUEPILL-STM32F103C8T6_MODULE-PB9)") (class "Default")
      (node (ref "BLUEPILL-STM32F103C8T6_MODULE") (pin "P$37") (pinfunction "PB9_P$37") (pintype "bidirectional"))
      (node (ref "J15") (pin "17") (pinfunction "17_17") (pintype "passive"))
    )
    (net (code "43") (name "Net-(BLUEPILL-STM32F103C8T6_MODULE-PB10{slash}TX3{slash}SCL2)") (class "Default")
      (node (ref "BLUEPILL-STM32F103C8T6_MODULE") (pin "P$15") (pinfunction "PB10/TX3/SCL2_P$15") (pintype "bidirectional"))
      (node (ref "J14") (pin "15") (pinfunction "15_15") (pintype "passive"))
    )
    (net (code "44") (name "Net-(BLUEPILL-STM32F103C8T6_MODULE-PB11{slash}RX3{slash}SDA2)") (class "Default")
      (node (ref "BLUEPILL-STM32F103C8T6_MODULE") (pin "P$16") (pinfunction "PB11/RX3/SDA2_P$16") (pintype "bidirectional"))
      (node (ref "J14") (pin "16") (pinfunction "16_16") (pintype "passive"))
    )
    (net (code "45") (name "Net-(BLUEPILL-STM32F103C8T6_MODULE-PB12{slash}SS2)") (class "Default")
      (node (ref "BLUEPILL-STM32F103C8T6_MODULE") (pin "P$21") (pinfunction "PB12/SS2_P$21") (pintype "bidirectional"))
      (node (ref "J15") (pin "1") (pinfunction "1_1") (pintype "passive"))
    )
    (net (code "46") (name "Net-(BLUEPILL-STM32F103C8T6_MODULE-PB13{slash}SCK2)") (class "Default")
      (node (ref "BLUEPILL-STM32F103C8T6_MODULE") (pin "P$22") (pinfunction "PB13/SCK2_P$22") (pintype "bidirectional"))
      (node (ref "J15") (pin "2") (pinfunction "2_2") (pintype "passive"))
    )
    (net (code "47") (name "Net-(BLUEPILL-STM32F103C8T6_MODULE-PB14{slash}MIS02)") (class "Default")
      (node (ref "BLUEPILL-STM32F103C8T6_MODULE") (pin "P$23") (pinfunction "PB14/MIS02_P$23") (pintype "bidirectional"))
      (node (ref "J15") (pin "3") (pinfunction "3_3") (pintype "passive"))
    )
    (net (code "48") (name "Net-(BLUEPILL-STM32F103C8T6_MODULE-PB15{slash}MOSI2)") (class "Default")
      (node (ref "BLUEPILL-STM32F103C8T6_MODULE") (pin "P$24") (pinfunction "PB15/MOSI2_P$24") (pintype "bidirectional"))
      (node (ref "J15") (pin "4") (pinfunction "4_4") (pintype "passive"))
    )
    (net (code "49") (name "Net-(BLUEPILL-STM32F103C8T6_MODULE-PC13)") (class "Default")
      (node (ref "BLUEPILL-STM32F103C8T6_MODULE") (pin "P$2") (pinfunction "PC13_P$2") (pintype "bidirectional"))
      (node (ref "J14") (pin "2") (pinfunction "2_2") (pintype "passive"))
    )
    (net (code "50") (name "Net-(BLUEPILL-STM32F103C8T6_MODULE-PC14)") (class "Default")
      (node (ref "BLUEPILL-STM32F103C8T6_MODULE") (pin "P$3") (pinfunction "PC14_P$3") (pintype "bidirectional"))
      (node (ref "J14") (pin "3") (pinfunction "3_3") (pintype "passive"))
    )
    (net (code "51") (name "Net-(BLUEPILL-STM32F103C8T6_MODULE-PC15)") (class "Default")
      (node (ref "BLUEPILL-STM32F103C8T6_MODULE") (pin "P$4") (pinfunction "PC15_P$4") (pintype "bidirectional"))
      (node (ref "J14") (pin "4") (pinfunction "4_4") (pintype "passive"))
    )
    (net (code "52") (name "Net-(BLUEPILL-STM32F103C8T6_MODULE-RESET)") (class "Default")
      (node (ref "BLUEPILL-STM32F103C8T6_MODULE") (pin "P$17") (pinfunction "RESET_P$17") (pintype "bidirectional"))
      (node (ref "J14") (pin "17") (pinfunction "17_17") (pintype "passive"))
    )
    (net (code "53") (name "Net-(BLUEPILL-STM32F103C8T6_MODULE-VBAT)") (class "Default")
      (node (ref "BLUEPILL-STM32F103C8T6_MODULE") (pin "P$1") (pinfunction "VBAT_P$1") (pintype "bidirectional"))
      (node (ref "J14") (pin "1") (pinfunction "1_1") (pintype "passive"))
    )
    (net (code "54") (name "Net-(IC1-HO)") (class "Default")
      (node (ref "IC1") (pin "8") (pinfunction "HO_8") (pintype "output"))
      (node (ref "R1") (pin "1") (pinfunction "1_1") (pintype "passive"))
    )
    (net (code "55") (name "Net-(IC1-LO)") (class "Default")
      (node (ref "IC1") (pin "1") (pinfunction "LO_1") (pintype "output"))
      (node (ref "J2") (pin "1") (pinfunction "1_1") (pintype "passive"))
    )
    (net (code "56") (name "Net-(IC2-HO)") (class "Default")
      (node (ref "IC2") (pin "8") (pinfunction "HO_8") (pintype "output"))
      (node (ref "R21") (pin "1") (pinfunction "1_1") (pintype "passive"))
    )
    (net (code "57") (name "Net-(IC2-LIN)") (class "Default")
      (node (ref "IC2") (pin "14") (pinfunction "LIN_14") (pintype "input"))
      (node (ref "R16") (pin "1") (pinfunction "1_1") (pintype "passive"))
    )
    (net (code "58") (name "Net-(IC2-LO)") (class "Default")
      (node (ref "IC2") (pin "1") (pinfunction "LO_1") (pintype "output"))
      (node (ref "R28") (pin "1") (pinfunction "1_1") (pintype "passive"))
    )
    (net (code "59") (name "Net-(IC4-+IN)") (class "Default")
      (node (ref "IC4") (pin "3") (pinfunction "+IN_3") (pintype "input"))
      (node (ref "R29") (pin "1") (pinfunction "1_1") (pintype "passive"))
      (node (ref "R37") (pin "1") (pinfunction "1_1") (pintype "passive"))
    )
    (net (code "60") (name "Net-(IC4--IN)") (class "Default")
      (node (ref "IC4") (pin "4") (pinfunction "-IN_4") (pintype "input"))
      (node (ref "R32") (pin "2") (pinfunction "2_2") (pintype "passive"))
      (node (ref "R33") (pin "1") (pinfunction "1_1") (pintype "passive"))
    )
    (net (code "61") (name "Net-(IC4-OUT)") (class "Default")
      (node (ref "IC4") (pin "1") (pinfunction "OUT_1") (pintype "output"))
      (node (ref "R33") (pin "2") (pinfunction "2_2") (pintype "passive"))
      (node (ref "R34") (pin "1") (pinfunction "1_1") (pintype "passive"))
    )
    (net (code "62") (name "Net-(IC5-HO)") (class "Default")
      (node (ref "IC5") (pin "8") (pinfunction "HO_8") (pintype "output"))
      (node (ref "J3") (pin "1") (pinfunction "1_1") (pintype "passive"))
    )
    (net (code "63") (name "Net-(IC5-LO)") (class "Default")
      (node (ref "IC5") (pin "1") (pinfunction "LO_1") (pintype "output"))
      (node (ref "J4") (pin "1") (pinfunction "1_1") (pintype "passive"))
    )
    (net (code "64") (name "Net-(J2-Pad2)") (class "Default")
      (node (ref "J2") (pin "2") (pinfunction "2_2") (pintype "passive"))
      (node (ref "R2") (pin "1") (pinfunction "1_1") (pintype "passive"))
    )
    (net (code "65") (name "Net-(J3-Pad2)") (class "Default")
      (node (ref "J3") (pin "2") (pinfunction "2_2") (pintype "passive"))
      (node (ref "R9") (pin "1") (pinfunction "1_1") (pintype "passive"))
    )
    (net (code "66") (name "Net-(J4-Pad2)") (class "Default")
      (node (ref "J4") (pin "2") (pinfunction "2_2") (pintype "passive"))
      (node (ref "R10") (pin "1") (pinfunction "1_1") (pintype "passive"))
    )
    (net (code "67") (name "Net-(J9-Pad1)") (class "Default")
      (node (ref "J9") (pin "1") (pinfunction "1_1") (pintype "passive"))
      (node (ref "R35") (pin "2") (pinfunction "2_2") (pintype "passive"))
    )
    (net (code "68") (name "Net-(R20-Pad1)") (class "Default")
      (node (ref "R20") (pin "1") (pinfunction "1_1") (pintype "passive"))
      (node (ref "R3") (pin "2") (pinfunction "2_2") (pintype "passive"))
    )
    (net (code "69") (name "Net-(R22-Pad1)") (class "Default")
      (node (ref "R22") (pin "1") (pinfunction "1_1") (pintype "passive"))
      (node (ref "R28") (pin "2") (pinfunction "2_2") (pintype "passive"))
    )
    (net (code "70") (name "Net-(R23-Pad2)") (class "Default")
      (node (ref "R23") (pin "2") (pinfunction "2_2") (pintype "passive"))
      (node (ref "R8") (pin "2") (pinfunction "2_2") (pintype "passive"))
    )
    (net (code "71") (name "Net-(U$1A-G)") (class "Default")
      (node (ref "R1") (pin "2") (pinfunction "2_2") (pintype "passive"))
      (node (ref "R5") (pin "2") (pinfunction "2_2") (pintype "passive"))
      (node (ref "U$1") (pin "4") (pinfunction "G_4") (pintype "input"))
    )
    (net (code "72") (name "Net-(U$1B-G)") (class "Default")
      (node (ref "R2") (pin "2") (pinfunction "2_2") (pintype "passive"))
      (node (ref "R6") (pin "1") (pinfunction "1_1") (pintype "passive"))
      (node (ref "U$1") (pin "2") (pinfunction "G_2") (pintype "input"))
    )
    (net (code "73") (name "Net-(U$10A-G)") (class "Default")
      (node (ref "R21") (pin "2") (pinfunction "2_2") (pintype "passive"))
      (node (ref "R25") (pin "2") (pinfunction "2_2") (pintype "passive"))
      (node (ref "U$10") (pin "4") (pinfunction "G_4") (pintype "input"))
    )
    (net (code "74") (name "Net-(U$10B-G)") (class "Default")
      (node (ref "R22") (pin "2") (pinfunction "2_2") (pintype "passive"))
      (node (ref "R26") (pin "1") (pinfunction "1_1") (pintype "passive"))
      (node (ref "U$10") (pin "2") (pinfunction "G_2") (pintype "input"))
    )
    (net (code "75") (name "Net-(U$16A-G)") (class "Default")
      (node (ref "R13") (pin "2") (pinfunction "2_2") (pintype "passive"))
      (node (ref "R9") (pin "2") (pinfunction "2_2") (pintype "passive"))
      (node (ref "U$16") (pin "4") (pinfunction "G_4") (pintype "input"))
    )
    (net (code "76") (name "Net-(U$16B-G)") (class "Default")
      (node (ref "R10") (pin "2") (pinfunction "2_2") (pintype "passive"))
      (node (ref "R14") (pin "1") (pinfunction "1_1") (pintype "passive"))
      (node (ref "U$16") (pin "2") (pinfunction "G_2") (pintype "input"))
    )
    (net (code "77") (name "unconnected-(IC3-GND-Pad2@1)") (class "Default")
      (node (ref "IC3") (pin "2@1") (pinfunction "GND_2@1") (pintype "passive"))
    )
  )
)
